# IO4-QuadOD.net
KiCad netlist of a schematic drawn in EAGLE
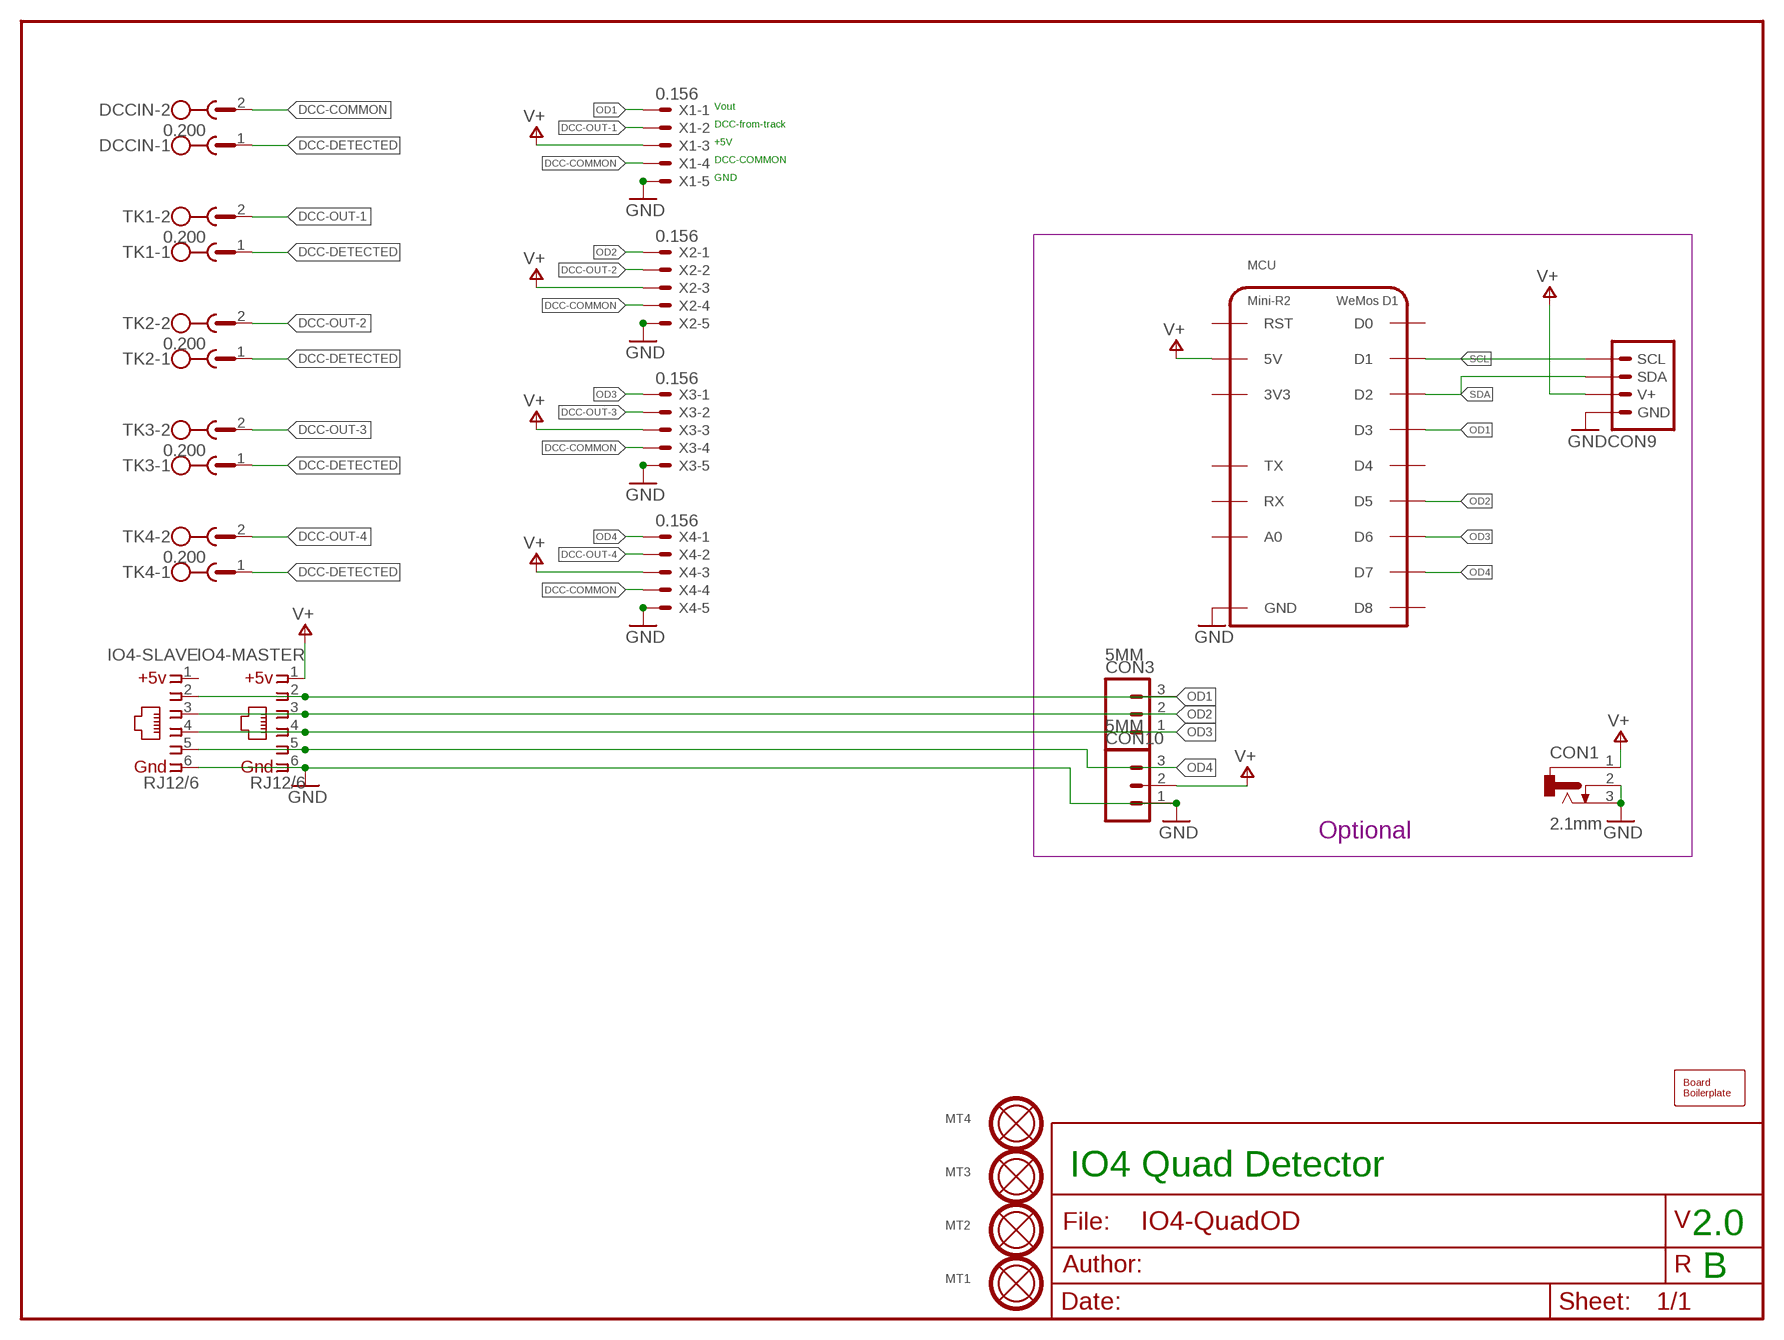
[diagram p0: schematic, sheet 1]

(export (version "E")
  (design (tool "Eeschema 10.0.6"))
  (components
    (comp (ref "BOARD1")
      (value "BOARD")
      (footprint "eagle-import:BOARD-SEEED10X10-NOHOLES")
      (libsource (lib "eagle-import") (part "BOARD100X100-NOHOLES"))
    )
    (comp (ref "CON1")
      (value "2.1mm")
      (footprint "eagle-import:DCJ0202")
      (libsource (lib "eagle-import") (part "CONNECTOR-DC-POWER-RA"))
    )
    (comp (ref "CON3")
      (value "5MM")
      (footprint "eagle-import:SCREWTERMINAL-5MM-3")
      (libsource (lib "eagle-import") (part "CONNECTOR-M035MM-LOCK"))
    )
    (comp (ref "CON9")
      (value "CONNECTOR-I2CLEFT")
      (footprint "eagle-import:I2C-L")
      (libsource (lib "eagle-import") (part "CONNECTOR-I2CLEFT"))
    )
    (comp (ref "CON10")
      (value "5MM")
      (footprint "eagle-import:SCREWTERMINAL-5MM-3")
      (libsource (lib "eagle-import") (part "CONNECTOR-M035MM-LOCK"))
    )
    (comp (ref "DCCIN")
      (value "0.200")
      (footprint "eagle-import:MSTBA2")
      (fields (field (name "MF") "FARNELL") (field (name "MPN") "1757242"))
      (libsource (lib "eagle-import") (part "CONNECTOR-MSTBA2-ORIG"))
    )
    (comp (ref "IO4-MASTER")
      (value "RJ12/6")
      (footprint "eagle-import:RJ25-INVERTED")
      (libsource (lib "eagle-import") (part "CONNECTOR-IO4INV"))
    )
    (comp (ref "IO4-SLAVE")
      (value "RJ12/6")
      (footprint "eagle-import:RJ25-INVERTED")
      (libsource (lib "eagle-import") (part "CONNECTOR-IO4INV"))
    )
    (comp (ref "MCU")
      (value "Mini-R2")
      (footprint "eagle-import:WEMOS-D1")
      (libsource (lib "eagle-import") (part "WEMOS-D1V1"))
    )
    (comp (ref "MT1")
      (value "MOUNTINGHOLE")
      (footprint "eagle-import:MOUNTINGHOLE")
      (libsource (lib "eagle-import") (part "MOUNTINGHOLE"))
    )
    (comp (ref "MT2")
      (value "MOUNTINGHOLE")
      (footprint "eagle-import:MOUNTINGHOLE")
      (libsource (lib "eagle-import") (part "MOUNTINGHOLE"))
    )
    (comp (ref "MT3")
      (value "MOUNTINGHOLE")
      (footprint "eagle-import:MOUNTINGHOLE")
      (libsource (lib "eagle-import") (part "MOUNTINGHOLE"))
    )
    (comp (ref "MT4")
      (value "MOUNTINGHOLE")
      (footprint "eagle-import:MOUNTINGHOLE")
      (libsource (lib "eagle-import") (part "MOUNTINGHOLE"))
    )
    (comp (ref "TK1")
      (value "0.200")
      (footprint "eagle-import:MSTBA2")
      (fields (field (name "MF") "FARNELL") (field (name "MPN") "1757242"))
      (libsource (lib "eagle-import") (part "CONNECTOR-MSTBA2-ORIG"))
    )
    (comp (ref "TK2")
      (value "0.200")
      (footprint "eagle-import:MSTBA2")
      (fields (field (name "MF") "FARNELL") (field (name "MPN") "1757242"))
      (libsource (lib "eagle-import") (part "CONNECTOR-MSTBA2-ORIG"))
    )
    (comp (ref "TK3")
      (value "0.200")
      (footprint "eagle-import:MSTBA2")
      (fields (field (name "MF") "FARNELL") (field (name "MPN") "1757242"))
      (libsource (lib "eagle-import") (part "CONNECTOR-MSTBA2-ORIG"))
    )
    (comp (ref "TK4")
      (value "0.200")
      (footprint "eagle-import:MSTBA2")
      (fields (field (name "MF") "FARNELL") (field (name "MPN") "1757242"))
      (libsource (lib "eagle-import") (part "CONNECTOR-MSTBA2-ORIG"))
    )
    (comp (ref "X1")
      (value "0.156")
      (footprint "eagle-import:KK-156-5")
      (libsource (lib "eagle-import") (part "KK-156-5"))
    )
    (comp (ref "X2")
      (value "0.156")
      (footprint "eagle-import:KK-156-5")
      (libsource (lib "eagle-import") (part "KK-156-5"))
    )
    (comp (ref "X3")
      (value "0.156")
      (footprint "eagle-import:KK-156-5")
      (libsource (lib "eagle-import") (part "KK-156-5"))
    )
    (comp (ref "X4")
      (value "0.156")
      (footprint "eagle-import:KK-156-5")
      (libsource (lib "eagle-import") (part "KK-156-5"))
    )
  )
  (nets
    (net (code "1") (name "/1") (class "Default")
      (node (ref "IO4-SLAVE") (pin "1") (pinfunction "1_1") (pintype "power_in"))
    )
    (net (code "2") (name "DCC-COMMON") (class "Default")
      (node (ref "DCCIN") (pin "2") (pinfunction "1_2") (pintype "passive"))
      (node (ref "X1") (pin "4") (pinfunction "S_4") (pintype "passive"))
      (node (ref "X2") (pin "4") (pinfunction "S_4") (pintype "passive"))
      (node (ref "X3") (pin "4") (pinfunction "S_4") (pintype "passive"))
      (node (ref "X4") (pin "4") (pinfunction "S_4") (pintype "passive"))
    )
    (net (code "3") (name "DCC-DETECTED") (class "Default")
      (node (ref "DCCIN") (pin "1") (pinfunction "1_1") (pintype "passive"))
      (node (ref "TK1") (pin "1") (pinfunction "1_1") (pintype "passive"))
      (node (ref "TK2") (pin "1") (pinfunction "1_1") (pintype "passive"))
      (node (ref "TK3") (pin "1") (pinfunction "1_1") (pintype "passive"))
      (node (ref "TK4") (pin "1") (pinfunction "1_1") (pintype "passive"))
    )
    (net (code "4") (name "DCC-OUT-1") (class "Default")
      (node (ref "TK1") (pin "2") (pinfunction "1_2") (pintype "passive"))
      (node (ref "X1") (pin "2") (pinfunction "S_2") (pintype "passive"))
    )
    (net (code "5") (name "DCC-OUT-2") (class "Default")
      (node (ref "TK2") (pin "2") (pinfunction "1_2") (pintype "passive"))
      (node (ref "X2") (pin "2") (pinfunction "S_2") (pintype "passive"))
    )
    (net (code "6") (name "DCC-OUT-3") (class "Default")
      (node (ref "TK3") (pin "2") (pinfunction "1_2") (pintype "passive"))
      (node (ref "X3") (pin "2") (pinfunction "S_2") (pintype "passive"))
    )
    (net (code "7") (name "DCC-OUT-4") (class "Default")
      (node (ref "TK4") (pin "2") (pinfunction "1_2") (pintype "passive"))
      (node (ref "X4") (pin "2") (pinfunction "S_2") (pintype "passive"))
    )
    (net (code "8") (name "GND") (class "Default")
      (node (ref "CON1") (pin "2") (pinfunction "2_2") (pintype "passive"))
      (node (ref "CON1") (pin "3") (pinfunction "3_3") (pintype "passive"))
      (node (ref "CON10") (pin "1") (pinfunction "1_1") (pintype "passive"))
      (node (ref "CON9") (pin "GND") (pinfunction "GND_GND") (pintype "passive"))
      (node (ref "CON9") (pin "GND@1") (pinfunction "GND_GND@1") (pintype "passive"))
      (node (ref "IO4-MASTER") (pin "6") (pinfunction "6_6") (pintype "power_in"))
      (node (ref "IO4-SLAVE") (pin "6") (pinfunction "6_6") (pintype "power_in"))
      (node (ref "MCU") (pin "GND") (pinfunction "GND_GND") (pintype "bidirectional"))
      (node (ref "X1") (pin "5") (pinfunction "S_5") (pintype "passive"))
      (node (ref "X2") (pin "5") (pinfunction "S_5") (pintype "passive"))
      (node (ref "X3") (pin "5") (pinfunction "S_5") (pintype "passive"))
      (node (ref "X4") (pin "5") (pinfunction "S_5") (pintype "passive"))
    )
    (net (code "9") (name "OD1") (class "Default")
      (node (ref "CON3") (pin "3") (pinfunction "3_3") (pintype "passive"))
      (node (ref "IO4-MASTER") (pin "2") (pinfunction "2_2") (pintype "passive"))
      (node (ref "IO4-SLAVE") (pin "2") (pinfunction "2_2") (pintype "passive"))
      (node (ref "MCU") (pin "D3") (pinfunction "D3_D3") (pintype "bidirectional"))
      (node (ref "X1") (pin "1") (pinfunction "S_1") (pintype "passive"))
    )
    (net (code "10") (name "OD2") (class "Default")
      (node (ref "CON3") (pin "2") (pinfunction "2_2") (pintype "passive"))
      (node (ref "IO4-MASTER") (pin "3") (pinfunction "3_3") (pintype "passive"))
      (node (ref "IO4-SLAVE") (pin "3") (pinfunction "3_3") (pintype "passive"))
      (node (ref "MCU") (pin "D5") (pinfunction "D5_D5") (pintype "bidirectional"))
      (node (ref "X2") (pin "1") (pinfunction "S_1") (pintype "passive"))
    )
    (net (code "11") (name "OD3") (class "Default")
      (node (ref "CON3") (pin "1") (pinfunction "1_1") (pintype "passive"))
      (node (ref "IO4-MASTER") (pin "4") (pinfunction "4_4") (pintype "passive"))
      (node (ref "IO4-SLAVE") (pin "4") (pinfunction "4_4") (pintype "passive"))
      (node (ref "MCU") (pin "D6") (pinfunction "D6_D6") (pintype "bidirectional"))
      (node (ref "X3") (pin "1") (pinfunction "S_1") (pintype "passive"))
    )
    (net (code "12") (name "OD4") (class "Default")
      (node (ref "CON10") (pin "3") (pinfunction "3_3") (pintype "passive"))
      (node (ref "IO4-MASTER") (pin "5") (pinfunction "5_5") (pintype "passive"))
      (node (ref "IO4-SLAVE") (pin "5") (pinfunction "5_5") (pintype "passive"))
      (node (ref "MCU") (pin "D7") (pinfunction "D7_D7") (pintype "bidirectional"))
      (node (ref "X4") (pin "1") (pinfunction "S_1") (pintype "passive"))
    )
    (net (code "13") (name "SCL") (class "Default")
      (node (ref "CON9") (pin "SCL") (pinfunction "SCL_SCL") (pintype "passive"))
      (node (ref "CON9") (pin "SCL@1") (pinfunction "SCL_SCL@1") (pintype "passive"))
      (node (ref "MCU") (pin "D1") (pinfunction "D1_D1") (pintype "bidirectional"))
    )
    (net (code "14") (name "SDA") (class "Default")
      (node (ref "CON9") (pin "SDA") (pinfunction "SDA_SDA") (pintype "passive"))
      (node (ref "CON9") (pin "SDA@1") (pinfunction "SDA_SDA@1") (pintype "passive"))
      (node (ref "MCU") (pin "D2") (pinfunction "D2_D2") (pintype "bidirectional"))
    )
    (net (code "15") (name "V+") (class "Default")
      (node (ref "CON1") (pin "1") (pinfunction "1_1") (pintype "passive"))
      (node (ref "CON10") (pin "2") (pinfunction "2_2") (pintype "passive"))
      (node (ref "CON9") (pin "V+") (pinfunction "V+_V+") (pintype "passive"))
      (node (ref "CON9") (pin "V+@1") (pinfunction "V+_V+@1") (pintype "passive"))
      (node (ref "IO4-MASTER") (pin "1") (pinfunction "1_1") (pintype "power_in"))
      (node (ref "MCU") (pin "5V") (pinfunction "5V_5V") (pintype "bidirectional"))
      (node (ref "X1") (pin "3") (pinfunction "S_3") (pintype "passive"))
      (node (ref "X2") (pin "3") (pinfunction "S_3") (pintype "passive"))
      (node (ref "X3") (pin "3") (pinfunction "S_3") (pintype "passive"))
      (node (ref "X4") (pin "3") (pinfunction "S_3") (pintype "passive"))
    )
    (net (code "16") (name "unconnected-(MCU-Pad3V3)") (class "Default")
      (node (ref "MCU") (pin "3V3") (pinfunction "3V3_3V3") (pintype "bidirectional"))
    )
    (net (code "17") (name "unconnected-(MCU-PadA0)") (class "Default")
      (node (ref "MCU") (pin "A0") (pinfunction "A0_A0") (pintype "bidirectional"))
    )
    (net (code "18") (name "unconnected-(MCU-PadD0)") (class "Default")
      (node (ref "MCU") (pin "D0") (pinfunction "D0_D0") (pintype "bidirectional"))
    )
    (net (code "19") (name "unconnected-(MCU-PadD4)") (class "Default")
      (node (ref "MCU") (pin "D4") (pinfunction "D4_D4") (pintype "bidirectional"))
    )
    (net (code "20") (name "unconnected-(MCU-PadD8)") (class "Default")
      (node (ref "MCU") (pin "D8") (pinfunction "D8_D8") (pintype "bidirectional"))
    )
    (net (code "21") (name "unconnected-(MCU-PadRST)") (class "Default")
      (node (ref "MCU") (pin "RST") (pinfunction "RST_RST") (pintype "bidirectional"))
    )
    (net (code "22") (name "unconnected-(MCU-PadRX)") (class "Default")
      (node (ref "MCU") (pin "RX") (pinfunction "RX_RX") (pintype "bidirectional"))
    )
    (net (code "23") (name "unconnected-(MCU-PadTX)") (class "Default")
      (node (ref "MCU") (pin "TX") (pinfunction "TX_TX") (pintype "bidirectional"))
    )
  )
)
